# 0116.net
KiCad netlist of a schematic drawn in EAGLE
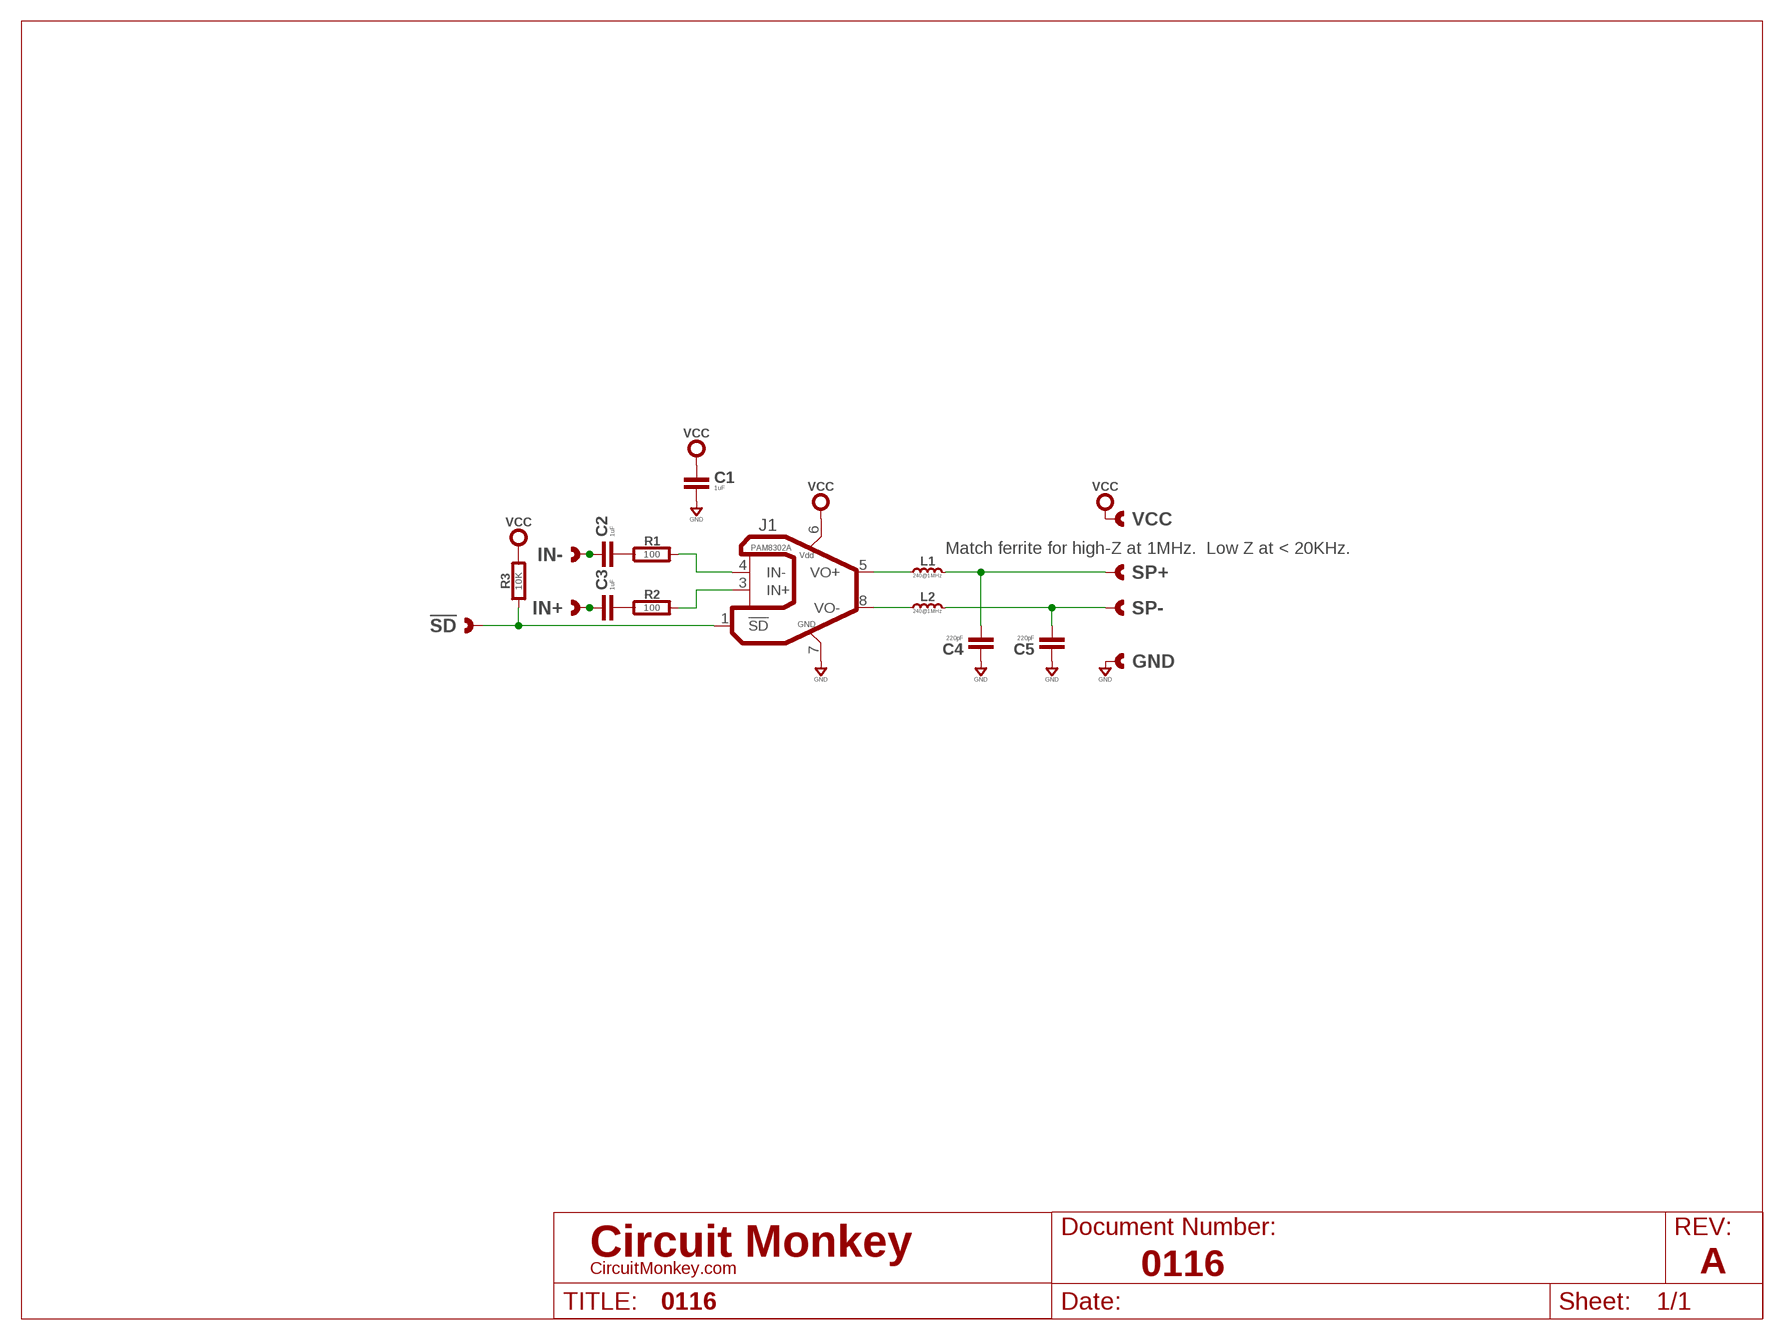
[diagram p0: schematic, sheet 1]

(export (version "E")
  (design (tool "Eeschema 10.0.6"))
  (components
    (comp (ref "!SD")
      (value "CAST-01X12.00MM")
      (footprint "eagle-import:CAST01-2.00MM")
      (libsource (lib "eagle-import") (part "CAST-01X12.00MM"))
    )
    (comp (ref "C1")
      (value "1uF")
      (footprint "eagle-import:0402-CAP")
      (libsource (lib "eagle-import") (part "CAPACITOR0402"))
    )
    (comp (ref "C2")
      (value "1uF")
      (footprint "eagle-import:0402-CAP")
      (libsource (lib "eagle-import") (part "CAPACITOR0402"))
    )
    (comp (ref "C3")
      (value "1uF")
      (footprint "eagle-import:0402-CAP")
      (libsource (lib "eagle-import") (part "CAPACITOR0402"))
    )
    (comp (ref "C4")
      (value "220pF")
      (footprint "eagle-import:0402-CAP")
      (libsource (lib "eagle-import") (part "CAPACITOR0402"))
    )
    (comp (ref "C5")
      (value "220pF")
      (footprint "eagle-import:0402-CAP")
      (libsource (lib "eagle-import") (part "CAPACITOR0402"))
    )
    (comp (ref "GND")
      (value "CAST-01X12.00MM")
      (footprint "eagle-import:CAST01-2.00MM")
      (libsource (lib "eagle-import") (part "CAST-01X12.00MM"))
    )
    (comp (ref "IN+")
      (value "CAST-01X12.00MM")
      (footprint "eagle-import:CAST01-2.00MM")
      (libsource (lib "eagle-import") (part "CAST-01X12.00MM"))
    )
    (comp (ref "IN-")
      (value "CAST-01X12.00MM")
      (footprint "eagle-import:CAST01-2.00MM")
      (libsource (lib "eagle-import") (part "CAST-01X12.00MM"))
    )
    (comp (ref "J1")
      (value "PAM8302A")
      (footprint "eagle-import:DFN-8-3X3")
      (fields (field (name "MFR") "Diodes, Inc.") (field (name "MPN") "PAM8302AAYC"))
      (libsource (lib "eagle-import") (part "PAM8302ADFN-3X3"))
    )
    (comp (ref "L1")
      (value "240@1MHz")
      (footprint "eagle-import:0402-IND")
      (fields (field (name "MFR") "TDK") (field (name "MPN") "MMZ1005S241HT000"))
      (libsource (lib "eagle-import") (part "FERRITE240OHM-600MA-0402"))
    )
    (comp (ref "L2")
      (value "240@1MHz")
      (footprint "eagle-import:0402-IND")
      (fields (field (name "MFR") "TDK") (field (name "MPN") "MMZ1005S241HT000"))
      (libsource (lib "eagle-import") (part "FERRITE240OHM-600MA-0402"))
    )
    (comp (ref "R1")
      (value "100")
      (footprint "eagle-import:0402-RES")
      (libsource (lib "eagle-import") (part "RESISTOR0402"))
    )
    (comp (ref "R2")
      (value "100")
      (footprint "eagle-import:0402-RES")
      (libsource (lib "eagle-import") (part "RESISTOR0402"))
    )
    (comp (ref "R3")
      (value "10K")
      (footprint "eagle-import:0402-RES")
      (libsource (lib "eagle-import") (part "RESISTOR0402"))
    )
    (comp (ref "SP+")
      (value "CAST-01X12.00MM")
      (footprint "eagle-import:CAST01-2.00MM")
      (libsource (lib "eagle-import") (part "CAST-01X12.00MM"))
    )
    (comp (ref "SP-")
      (value "CAST-01X12.00MM")
      (footprint "eagle-import:CAST01-2.00MM")
      (libsource (lib "eagle-import") (part "CAST-01X12.00MM"))
    )
    (comp (ref "VCC")
      (value "CAST-01X12.00MM")
      (footprint "eagle-import:CAST01-2.00MM")
      (libsource (lib "eagle-import") (part "CAST-01X12.00MM"))
    )
  )
  (nets
    (net (code "1") (name "GND") (class "Default")
      (node (ref "C1") (pin "2") (pinfunction "2_2") (pintype "passive"))
      (node (ref "C4") (pin "1") (pinfunction "1_1") (pintype "passive"))
      (node (ref "C5") (pin "1") (pinfunction "1_1") (pintype "passive"))
      (node (ref "GND") (pin "1") (pinfunction "1_1") (pintype "bidirectional"))
      (node (ref "GND") (pin "P$1") (pinfunction "1_P$1") (pintype "bidirectional"))
      (node (ref "GND") (pin "P$2") (pinfunction "1_P$2") (pintype "bidirectional"))
      (node (ref "J1") (pin "7") (pinfunction "GND_7") (pintype "bidirectional"))
    )
    (net (code "2") (name "Net-(C2-Pad1)") (class "Default")
      (node (ref "C2") (pin "1") (pinfunction "1_1") (pintype "passive"))
      (node (ref "IN-") (pin "1") (pinfunction "1_1") (pintype "bidirectional"))
      (node (ref "IN-") (pin "P$1") (pinfunction "1_P$1") (pintype "bidirectional"))
      (node (ref "IN-") (pin "P$2") (pinfunction "1_P$2") (pintype "bidirectional"))
    )
    (net (code "3") (name "Net-(C2-Pad2)") (class "Default")
      (node (ref "C2") (pin "2") (pinfunction "2_2") (pintype "passive"))
      (node (ref "R1") (pin "1") (pinfunction "1_1") (pintype "passive"))
    )
    (net (code "4") (name "Net-(C3-Pad1)") (class "Default")
      (node (ref "C3") (pin "1") (pinfunction "1_1") (pintype "passive"))
      (node (ref "IN+") (pin "1") (pinfunction "1_1") (pintype "bidirectional"))
      (node (ref "IN+") (pin "P$1") (pinfunction "1_P$1") (pintype "bidirectional"))
      (node (ref "IN+") (pin "P$2") (pinfunction "1_P$2") (pintype "bidirectional"))
    )
    (net (code "5") (name "Net-(C3-Pad2)") (class "Default")
      (node (ref "C3") (pin "2") (pinfunction "2_2") (pintype "passive"))
      (node (ref "R2") (pin "1") (pinfunction "1_1") (pintype "passive"))
    )
    (net (code "6") (name "Net-(J1-IN+)") (class "Default")
      (node (ref "J1") (pin "3") (pinfunction "IN+_3") (pintype "bidirectional"))
      (node (ref "R2") (pin "2") (pinfunction "2_2") (pintype "passive"))
    )
    (net (code "7") (name "Net-(J1-IN-)") (class "Default")
      (node (ref "J1") (pin "4") (pinfunction "IN-_4") (pintype "bidirectional"))
      (node (ref "R1") (pin "2") (pinfunction "2_2") (pintype "passive"))
    )
    (net (code "8") (name "Net-(J1-VO+)") (class "Default")
      (node (ref "J1") (pin "5") (pinfunction "VO+_5") (pintype "bidirectional"))
      (node (ref "L1") (pin "3") (pinfunction "1_3") (pintype "passive"))
    )
    (net (code "9") (name "Net-(J1-VO-)") (class "Default")
      (node (ref "J1") (pin "8") (pinfunction "VO-_8") (pintype "bidirectional"))
      (node (ref "L2") (pin "3") (pinfunction "1_3") (pintype "passive"))
    )
    (net (code "10") (name "Net-(J1-~{SD})") (class "Default")
      (node (ref "!SD") (pin "1") (pinfunction "1_1") (pintype "bidirectional"))
      (node (ref "!SD") (pin "P$1") (pinfunction "1_P$1") (pintype "bidirectional"))
      (node (ref "!SD") (pin "P$2") (pinfunction "1_P$2") (pintype "bidirectional"))
      (node (ref "J1") (pin "1") (pinfunction "~{SD}_1") (pintype "bidirectional"))
      (node (ref "R3") (pin "1") (pinfunction "1_1") (pintype "passive"))
    )
    (net (code "11") (name "Net-(L1-2)") (class "Default")
      (node (ref "C4") (pin "2") (pinfunction "2_2") (pintype "passive"))
      (node (ref "L1") (pin "4") (pinfunction "2_4") (pintype "passive"))
      (node (ref "SP+") (pin "1") (pinfunction "1_1") (pintype "bidirectional"))
      (node (ref "SP+") (pin "P$1") (pinfunction "1_P$1") (pintype "bidirectional"))
      (node (ref "SP+") (pin "P$2") (pinfunction "1_P$2") (pintype "bidirectional"))
    )
    (net (code "12") (name "Net-(L2-2)") (class "Default")
      (node (ref "C5") (pin "2") (pinfunction "2_2") (pintype "passive"))
      (node (ref "L2") (pin "4") (pinfunction "2_4") (pintype "passive"))
      (node (ref "SP-") (pin "1") (pinfunction "1_1") (pintype "bidirectional"))
      (node (ref "SP-") (pin "P$1") (pinfunction "1_P$1") (pintype "bidirectional"))
      (node (ref "SP-") (pin "P$2") (pinfunction "1_P$2") (pintype "bidirectional"))
    )
    (net (code "13") (name "VCC") (class "Default")
      (node (ref "C1") (pin "1") (pinfunction "1_1") (pintype "passive"))
      (node (ref "J1") (pin "6") (pinfunction "VDD_6") (pintype "bidirectional"))
      (node (ref "R3") (pin "2") (pinfunction "2_2") (pintype "passive"))
      (node (ref "VCC") (pin "1") (pinfunction "1_1") (pintype "bidirectional"))
      (node (ref "VCC") (pin "P$1") (pinfunction "1_P$1") (pintype "bidirectional"))
      (node (ref "VCC") (pin "P$2") (pinfunction "1_P$2") (pintype "bidirectional"))
    )
  )
)
